# PTC_Thermistor_1K_VDiv.net
KiCad netlist of a schematic drawn in Altium Designer
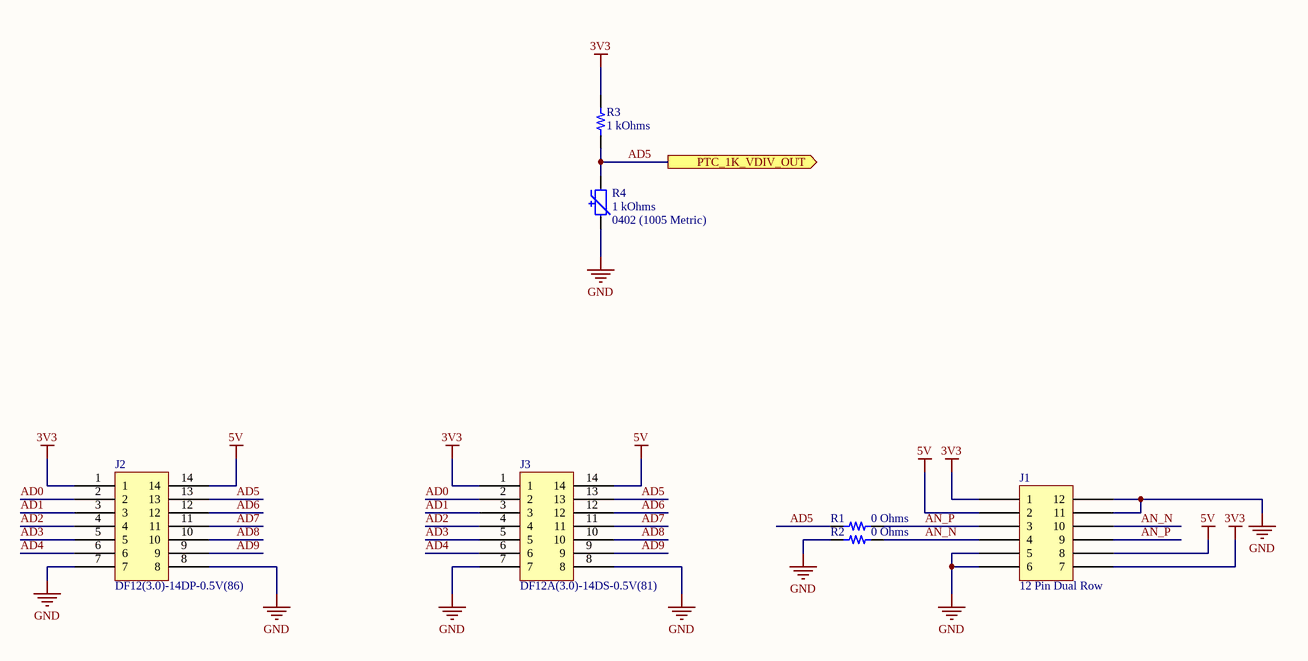
[diagram p0: PTC Thermistor 1K VDiv.SchDoc]

(export (version "E")
  (design (tool "Eeschema 10.0.6"))
  (components
    (comp (ref "J1")
      (value "12 Pin Dual Row")
      (footprint "TE 5650118-3 Card Edge")
      (libsource (lib "CelestialUseful") (part "12 Pin Dual Row"))
    )
    (comp (ref "J2")
      (value "DF12(3.0)-14DP-0.5V(86)")
      (footprint "HIROSE DF12 3.0-14DP-0.5V 86")
      (description "CONN HDR 14POS SMD GOLD")
      (fields (field (name "MANUFACTURER") "Hirose Electric Co Ltd"))
      (libsource (lib "altiumlibrary.com") (part "14 Pin Dual Row"))
    )
    (comp (ref "J3")
      (value "DF12A(3.0)-14DS-0.5V(81)")
      (footprint "HIROSE DF12A 3.0-14DS-0.5V 81")
      (description "CONN RCPT 14POS SMD GOLD")
      (fields (field (name "MANUFACTURER") "Hirose Electric Co Ltd"))
      (libsource (lib "altiumlibrary.com") (part "14 Pin Dual Row"))
    )
    (comp (ref "R1")
      (value "0 Ohms")
      (footprint "RES 0603_1608")
      (description "RES SMD 0 OHM JUMPER 1/10W 0603")
      (fields
        (field (name "PART NUMBER") "ERJ-3GEY0R00V")
        (field (name "MANUFACTURER") "Panasonic Electronic Components")
      )
      (libsource (lib "altiumlibrary.com") (part "Resistor"))
    )
    (comp (ref "R2")
      (value "0 Ohms")
      (footprint "RES 0603_1608")
      (description "RES SMD 0 OHM JUMPER 1/10W 0603")
      (fields
        (field (name "PART NUMBER") "ERJ-3GEY0R00V")
        (field (name "MANUFACTURER") "Panasonic Electronic Components")
      )
      (libsource (lib "altiumlibrary.com") (part "Resistor"))
    )
    (comp (ref "R3")
      (value "1 kOhms")
      (footprint "RES 0603_1608")
      (description "RES SMD 1K OHM 1% 1/10W 0603")
      (fields
        (field (name "PART NUMBER") "ERJ-3EKF1001V")
        (field (name "MANUFACTURER") "Panasonic Electronic Components")
      )
      (libsource (lib "altiumlibrary.com") (part "Resistor"))
    )
    (comp (ref "R4")
      (value "1 kOhms")
      (footprint "PTC 0402_1005")
      (description "THERMISTOR PTC 1K OHM 5% 0402")
      (fields
        (field (name "PART NUMBER") "PRF15AR102RB6RC")
        (field (name "MANUFACTURER") "Murata Electronics")
        (field (name "PACKAGE / CASE") "0402 (1005 Metric)")
      )
      (libsource (lib "altiumlibrary.com") (part "Thermistor PTC"))
    )
  )
  (nets
    (net (code "1") (name "/AD0") (class "Default")
      (node (ref "J2") (pin "2") (pinfunction "2_2") (pintype "passive"))
      (node (ref "J3") (pin "2") (pinfunction "2_2") (pintype "passive"))
    )
    (net (code "2") (name "/AD1") (class "Default")
      (node (ref "J2") (pin "3") (pinfunction "3_3") (pintype "passive"))
      (node (ref "J3") (pin "3") (pinfunction "3_3") (pintype "passive"))
    )
    (net (code "3") (name "/AD2") (class "Default")
      (node (ref "J2") (pin "4") (pinfunction "4_4") (pintype "passive"))
      (node (ref "J3") (pin "4") (pinfunction "4_4") (pintype "passive"))
    )
    (net (code "4") (name "/AD3") (class "Default")
      (node (ref "J2") (pin "5") (pinfunction "5_5") (pintype "passive"))
      (node (ref "J3") (pin "5") (pinfunction "5_5") (pintype "passive"))
    )
    (net (code "5") (name "/AD4") (class "Default")
      (node (ref "J2") (pin "6") (pinfunction "6_6") (pintype "passive"))
      (node (ref "J3") (pin "6") (pinfunction "6_6") (pintype "passive"))
    )
    (net (code "6") (name "/AD5") (class "Default")
      (node (ref "J2") (pin "13") (pinfunction "13_13") (pintype "passive"))
      (node (ref "J3") (pin "13") (pinfunction "13_13") (pintype "passive"))
      (node (ref "R1") (pin "1") (pinfunction "1_1") (pintype "passive"))
      (node (ref "R3") (pin "1") (pinfunction "1_1") (pintype "passive"))
      (node (ref "R4") (pin "1") (pinfunction "1_1") (pintype "passive"))
    )
    (net (code "7") (name "/AD6") (class "Default")
      (node (ref "J2") (pin "12") (pinfunction "12_12") (pintype "passive"))
      (node (ref "J3") (pin "12") (pinfunction "12_12") (pintype "passive"))
    )
    (net (code "8") (name "/AD7") (class "Default")
      (node (ref "J2") (pin "11") (pinfunction "11_11") (pintype "passive"))
      (node (ref "J3") (pin "11") (pinfunction "11_11") (pintype "passive"))
    )
    (net (code "9") (name "/AD8") (class "Default")
      (node (ref "J2") (pin "10") (pinfunction "10_10") (pintype "passive"))
      (node (ref "J3") (pin "10") (pinfunction "10_10") (pintype "passive"))
    )
    (net (code "10") (name "/AD9") (class "Default")
      (node (ref "J2") (pin "9") (pinfunction "9_9") (pintype "passive"))
      (node (ref "J3") (pin "9") (pinfunction "9_9") (pintype "passive"))
    )
    (net (code "11") (name "/AN_N") (class "Default")
      (node (ref "J1") (pin "10") (pinfunction "10_10") (pintype "passive"))
      (node (ref "J1") (pin "4") (pinfunction "4_4") (pintype "passive"))
      (node (ref "R2") (pin "2") (pinfunction "2_2") (pintype "passive"))
    )
    (net (code "12") (name "/AN_P") (class "Default")
      (node (ref "J1") (pin "3") (pinfunction "3_3") (pintype "passive"))
      (node (ref "J1") (pin "9") (pinfunction "9_9") (pintype "passive"))
      (node (ref "R1") (pin "2") (pinfunction "2_2") (pintype "passive"))
    )
    (net (code "13") (name "3V3") (class "Default")
      (node (ref "J1") (pin "1") (pinfunction "1_1") (pintype "passive"))
      (node (ref "J1") (pin "7") (pinfunction "7_7") (pintype "passive"))
      (node (ref "J2") (pin "1") (pinfunction "1_1") (pintype "passive"))
      (node (ref "J3") (pin "1") (pinfunction "1_1") (pintype "passive"))
      (node (ref "R3") (pin "2") (pinfunction "2_2") (pintype "passive"))
    )
    (net (code "14") (name "5V") (class "Default")
      (node (ref "J1") (pin "2") (pinfunction "2_2") (pintype "passive"))
      (node (ref "J1") (pin "8") (pinfunction "8_8") (pintype "passive"))
      (node (ref "J2") (pin "14") (pinfunction "14_14") (pintype "passive"))
      (node (ref "J3") (pin "14") (pinfunction "14_14") (pintype "passive"))
    )
    (net (code "15") (name "GND") (class "Default")
      (node (ref "J1") (pin "11") (pinfunction "11_11") (pintype "passive"))
      (node (ref "J1") (pin "12") (pinfunction "12_12") (pintype "passive"))
      (node (ref "J1") (pin "5") (pinfunction "5_5") (pintype "passive"))
      (node (ref "J1") (pin "6") (pinfunction "6_6") (pintype "passive"))
      (node (ref "J2") (pin "7") (pinfunction "7_7") (pintype "passive"))
      (node (ref "J2") (pin "8") (pinfunction "8_8") (pintype "passive"))
      (node (ref "J3") (pin "7") (pinfunction "7_7") (pintype "passive"))
      (node (ref "J3") (pin "8") (pinfunction "8_8") (pintype "passive"))
      (node (ref "R2") (pin "1") (pinfunction "1_1") (pintype "passive"))
      (node (ref "R4") (pin "2") (pinfunction "2_2") (pintype "passive"))
    )
  )
)
